# CAN.net
KiCad netlist of a schematic drawn in Altium Designer
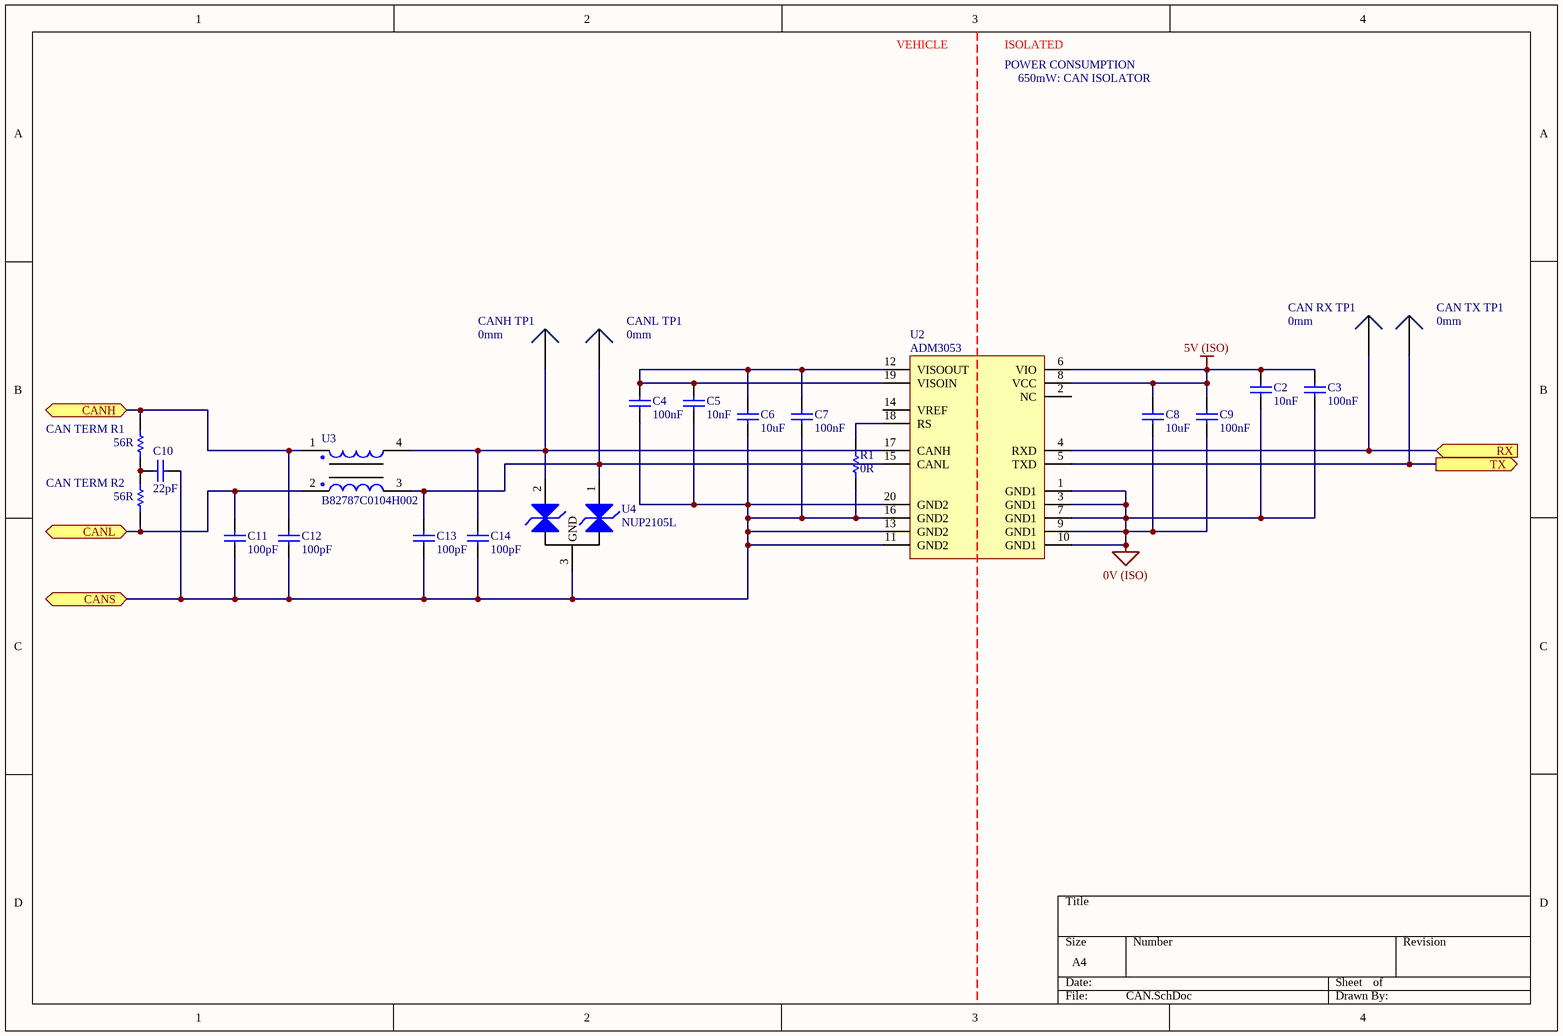
[diagram p0: CAN.SchDoc]

(export (version "E")
  (design (tool "Eeschema 10.0.6"))
  (components
    (comp (ref "C2")
      (value "10nF")
      (footprint "1206")
      (fields
        (field (name "PART NUMBER") "GCM3195C2A103JA16D")
        (field (name "TOLERANCE") "5%")
        (field (name "MANUFACTURER") "muRata")
      )
      (libsource (lib "ts_20-standard-library") (part "Capacitor"))
    )
    (comp (ref "C3")
      (value "100nF")
      (footprint "0805")
      (fields
        (field (name "PART NUMBER") "GCM21BR71E104KA37L")
        (field (name "TOLERANCE") "10%")
        (field (name "MANUFACTURER") "muRata")
      )
      (libsource (lib "ts_20-standard-library") (part "Capacitor"))
    )
    (comp (ref "C4")
      (value "100nF")
      (footprint "0805")
      (fields
        (field (name "PART NUMBER") "GCM21BR71E104KA37L")
        (field (name "TOLERANCE") "10%")
        (field (name "MANUFACTURER") "muRata")
      )
      (libsource (lib "ts_20-standard-library") (part "Capacitor"))
    )
    (comp (ref "C5")
      (value "10nF")
      (footprint "1206")
      (fields
        (field (name "PART NUMBER") "GCM3195C2A103JA16D")
        (field (name "TOLERANCE") "5%")
        (field (name "MANUFACTURER") "muRata")
      )
      (libsource (lib "ts_20-standard-library") (part "Capacitor"))
    )
    (comp (ref "C6")
      (value "10uF")
      (footprint "0805")
      (fields
        (field (name "PART NUMBER") "GRM21BR6YA106KE43L")
        (field (name "TOLERANCE") "10%")
        (field (name "MANUFACTURER") "muRata")
      )
      (libsource (lib "ts_20-standard-library") (part "Capacitor"))
    )
    (comp (ref "C7")
      (value "100nF")
      (footprint "0805")
      (fields
        (field (name "PART NUMBER") "GCM21BR71E104KA37L")
        (field (name "TOLERANCE") "10%")
        (field (name "MANUFACTURER") "muRata")
      )
      (libsource (lib "ts_20-standard-library") (part "Capacitor"))
    )
    (comp (ref "C8")
      (value "10uF")
      (footprint "0805")
      (fields
        (field (name "PART NUMBER") "GRM21BR6YA106KE43L")
        (field (name "TOLERANCE") "10%")
        (field (name "MANUFACTURER") "muRata")
      )
      (libsource (lib "ts_20-standard-library") (part "Capacitor"))
    )
    (comp (ref "C9")
      (value "100nF")
      (footprint "0805")
      (fields
        (field (name "PART NUMBER") "GCM21BR71E104KA37L")
        (field (name "TOLERANCE") "10%")
        (field (name "MANUFACTURER") "muRata")
      )
      (libsource (lib "ts_20-standard-library") (part "Capacitor"))
    )
    (comp (ref "C10")
      (value "22pF")
      (footprint "0805")
      (fields
        (field (name "PART NUMBER") "GCM21B5C1H220JA37L")
        (field (name "TOLERANCE") "5%")
        (field (name "MANUFACTURER") "muRata")
      )
      (libsource (lib "ts_20-standard-library") (part "Capacitor"))
    )
    (comp (ref "C11")
      (value "100pF")
      (footprint "0805")
      (fields
        (field (name "PART NUMBER") "GCM21B5C1H101JA37L")
        (field (name "TOLERANCE") "5%")
        (field (name "MANUFACTURER") "muRata")
      )
      (libsource (lib "ts_20-standard-library") (part "Capacitor"))
    )
    (comp (ref "C12")
      (value "100pF")
      (footprint "0805")
      (fields
        (field (name "PART NUMBER") "GCM21B5C1H101JA37L")
        (field (name "TOLERANCE") "5%")
        (field (name "MANUFACTURER") "muRata")
      )
      (libsource (lib "ts_20-standard-library") (part "Capacitor"))
    )
    (comp (ref "C13")
      (value "100pF")
      (footprint "0805")
      (fields
        (field (name "PART NUMBER") "GCM21B5C1H101JA37L")
        (field (name "TOLERANCE") "5%")
        (field (name "MANUFACTURER") "muRata")
      )
      (libsource (lib "ts_20-standard-library") (part "Capacitor"))
    )
    (comp (ref "C14")
      (value "100pF")
      (footprint "0805")
      (fields
        (field (name "PART NUMBER") "GCM21B5C1H101JA37L")
        (field (name "TOLERANCE") "5%")
        (field (name "MANUFACTURER") "muRata")
      )
      (libsource (lib "ts_20-standard-library") (part "Capacitor"))
    )
    (comp (ref "CAN RX TP1")
      (value "0mm")
      (footprint "SMD Test Point")
      (fields (field (name "PART NUMBER") "SMD Test Point") (field (name "CONTACT") "NA"))
      (libsource (lib "ts_20-standard-connectors") (part "Test Point"))
    )
    (comp (ref "CAN TERM R1")
      (value "56R")
      (footprint "0805")
      (fields
        (field (name "PART NUMBER") "RC0805FR0756RL")
        (field (name "MANUFACTURER") "YAGEO")
        (field (name "TOLERANCE") "0.01")
      )
      (libsource (lib "ts_20-standard-library") (part "Resistor"))
    )
    (comp (ref "CAN TERM R2")
      (value "56R")
      (footprint "0805")
      (fields
        (field (name "PART NUMBER") "RC0805FR0756RL")
        (field (name "MANUFACTURER") "YAGEO")
        (field (name "TOLERANCE") "0.01")
      )
      (libsource (lib "ts_20-standard-library") (part "Resistor"))
    )
    (comp (ref "CAN TX TP1")
      (value "0mm")
      (footprint "SMD Test Point")
      (fields (field (name "PART NUMBER") "SMD Test Point") (field (name "CONTACT") "NA"))
      (libsource (lib "ts_20-standard-connectors") (part "Test Point"))
    )
    (comp (ref "CANH TP1")
      (value "0mm")
      (footprint "SMD Test Point")
      (fields (field (name "PART NUMBER") "SMD Test Point") (field (name "CONTACT") "NA"))
      (libsource (lib "ts_20-standard-connectors") (part "Test Point"))
    )
    (comp (ref "CANL TP1")
      (value "0mm")
      (footprint "SMD Test Point")
      (fields (field (name "PART NUMBER") "SMD Test Point") (field (name "CONTACT") "NA"))
      (libsource (lib "ts_20-standard-connectors") (part "Test Point"))
    )
    (comp (ref "R1")
      (value "0R")
      (footprint "0805")
      (fields
        (field (name "PART NUMBER") "RC0805FR070RL")
        (field (name "MANUFACTURER") "YAGEO")
        (field (name "TOLERANCE") "0.01")
      )
      (libsource (lib "ts_20-standard-library") (part "Resistor"))
    )
    (comp (ref "U2")
      (value "ADM3053")
      (footprint "AD SOIC-W 20")
      (description "Isolated CAN Transceiver")
      (fields
        (field (name "MANUFACTURER") "Analogue Devices")
        (field (name "DIGIKEY PART NUMBER") "ADM3053BRWZ-ND")
      )
      (libsource (lib "ts_20-standard-library") (part "ADM3053"))
    )
    (comp (ref "U3")
      (value "B82787C0104H002")
      (footprint "TDK 4-PC Pad")
      (description "100µH @ 100kHz 2 Line Common Mode Choke Surface Mount 5.8 kOhms @ 10MHz 150mA DCR 2Ohm")
      (fields
        (field (name "MANUFACTURER") "EPCOS (TDK)")
        (field (name "DIGIKEY PART NUMBER") "495-4598-1-ND")
      )
      (libsource (lib "ts_20-standard-library") (part "B82787C0104H002"))
    )
    (comp (ref "U4")
      (value "NUP2105L")
      (footprint "ON SOT-23")
      (description "Dual Line CAN Bus Protector")
      (fields
        (field (name "MANUFACTURER") "ON Semiconductor")
        (field (name "DIGIKEY PART NUMBER") "NUP2105LT1GOSCT-ND")
      )
      (libsource (lib "ts_20-standard-library") (part "NUP2105L"))
    )
  )
  (nets
    (net (code "1") (name "/CANH") (class "Default")
      (node (ref "C12") (pin "2") (pinfunction "2_2") (pintype "passive"))
      (node (ref "CAN TERM R1") (pin "2") (pinfunction "2_2") (pintype "passive"))
      (node (ref "U3") (pin "1") (pinfunction "1_1") (pintype "passive"))
    )
    (net (code "2") (name "/CANL") (class "Default")
      (node (ref "C11") (pin "2") (pinfunction "2_2") (pintype "passive"))
      (node (ref "CAN TERM R2") (pin "1") (pinfunction "1_1") (pintype "passive"))
      (node (ref "U3") (pin "2") (pinfunction "2_2") (pintype "passive"))
    )
    (net (code "3") (name "/CANS") (class "Default")
      (node (ref "C10") (pin "1") (pinfunction "1_1") (pintype "passive"))
      (node (ref "C11") (pin "1") (pinfunction "1_1") (pintype "passive"))
      (node (ref "C12") (pin "1") (pinfunction "1_1") (pintype "passive"))
      (node (ref "C13") (pin "1") (pinfunction "1_1") (pintype "passive"))
      (node (ref "C14") (pin "1") (pinfunction "1_1") (pintype "passive"))
      (node (ref "C4") (pin "1") (pinfunction "1_1") (pintype "passive"))
      (node (ref "C5") (pin "1") (pinfunction "1_1") (pintype "passive"))
      (node (ref "C6") (pin "1") (pinfunction "1_1") (pintype "passive"))
      (node (ref "C7") (pin "1") (pinfunction "1_1") (pintype "passive"))
      (node (ref "R1") (pin "1") (pinfunction "1_1") (pintype "passive"))
      (node (ref "U2") (pin "11") (pinfunction "GND2_11") (pintype "passive"))
      (node (ref "U2") (pin "13") (pinfunction "GND2_13") (pintype "passive"))
      (node (ref "U2") (pin "16") (pinfunction "GND2_16") (pintype "passive"))
      (node (ref "U2") (pin "20") (pinfunction "GND2_20") (pintype "passive"))
      (node (ref "U4") (pin "3") (pinfunction "GND_3") (pintype "power_in"))
    )
    (net (code "4") (name "/RX") (class "Default")
      (node (ref "CAN RX TP1") (pin "1") (pinfunction "1_1") (pintype "passive"))
      (node (ref "U2") (pin "4") (pinfunction "RXD_4") (pintype "passive"))
    )
    (net (code "5") (name "/TX") (class "Default")
      (node (ref "CAN TX TP1") (pin "1") (pinfunction "1_1") (pintype "passive"))
      (node (ref "U2") (pin "5") (pinfunction "TXD_5") (pintype "passive"))
    )
    (net (code "6") (name "0V (ISO)") (class "Default")
      (node (ref "C2") (pin "1") (pinfunction "1_1") (pintype "passive"))
      (node (ref "C3") (pin "1") (pinfunction "1_1") (pintype "passive"))
      (node (ref "C8") (pin "1") (pinfunction "1_1") (pintype "passive"))
      (node (ref "C9") (pin "1") (pinfunction "1_1") (pintype "passive"))
      (node (ref "U2") (pin "1") (pinfunction "GND1_1") (pintype "passive"))
      (node (ref "U2") (pin "10") (pinfunction "GND1_10") (pintype "passive"))
      (node (ref "U2") (pin "3") (pinfunction "GND1_3") (pintype "passive"))
      (node (ref "U2") (pin "7") (pinfunction "GND1_7") (pintype "passive"))
      (node (ref "U2") (pin "9") (pinfunction "GND1_9") (pintype "passive"))
    )
    (net (code "7") (name "5V (ISO)") (class "Default")
      (node (ref "C2") (pin "2") (pinfunction "2_2") (pintype "passive"))
      (node (ref "C3") (pin "2") (pinfunction "2_2") (pintype "passive"))
      (node (ref "C8") (pin "2") (pinfunction "2_2") (pintype "passive"))
      (node (ref "C9") (pin "2") (pinfunction "2_2") (pintype "passive"))
      (node (ref "U2") (pin "6") (pinfunction "VIO_6") (pintype "passive"))
      (node (ref "U2") (pin "8") (pinfunction "VCC_8") (pintype "passive"))
    )
    (net (code "8") (name "Net-(C10-Pad2)") (class "Default")
      (node (ref "C10") (pin "2") (pinfunction "2_2") (pintype "passive"))
      (node (ref "CAN TERM R1") (pin "1") (pinfunction "1_1") (pintype "passive"))
      (node (ref "CAN TERM R2") (pin "2") (pinfunction "2_2") (pintype "passive"))
    )
    (net (code "9") (name "Net-(U2-CANH)") (class "Default")
      (node (ref "C14") (pin "2") (pinfunction "2_2") (pintype "passive"))
      (node (ref "CANH TP1") (pin "1") (pinfunction "1_1") (pintype "passive"))
      (node (ref "U2") (pin "17") (pinfunction "CANH_17") (pintype "passive"))
      (node (ref "U3") (pin "4") (pinfunction "4_4") (pintype "passive"))
      (node (ref "U4") (pin "2") (pinfunction "CAN_L_2") (pintype "passive"))
    )
    (net (code "10") (name "Net-(U2-CANL)") (class "Default")
      (node (ref "C13") (pin "2") (pinfunction "2_2") (pintype "passive"))
      (node (ref "CANL TP1") (pin "1") (pinfunction "1_1") (pintype "passive"))
      (node (ref "U2") (pin "15") (pinfunction "CANL_15") (pintype "passive"))
      (node (ref "U3") (pin "3") (pinfunction "3_3") (pintype "power_in"))
      (node (ref "U4") (pin "1") (pinfunction "CAN_H_1") (pintype "passive"))
    )
    (net (code "11") (name "Net-(U2-RS)") (class "Default")
      (node (ref "R1") (pin "2") (pinfunction "2_2") (pintype "passive"))
      (node (ref "U2") (pin "18") (pinfunction "RS_18") (pintype "passive"))
    )
    (net (code "12") (name "Net-(U2-VISOIN)") (class "Default")
      (node (ref "C4") (pin "2") (pinfunction "2_2") (pintype "passive"))
      (node (ref "C5") (pin "2") (pinfunction "2_2") (pintype "passive"))
      (node (ref "C6") (pin "2") (pinfunction "2_2") (pintype "passive"))
      (node (ref "C7") (pin "2") (pinfunction "2_2") (pintype "passive"))
      (node (ref "U2") (pin "12") (pinfunction "VISOOUT_12") (pintype "passive"))
      (node (ref "U2") (pin "19") (pinfunction "VISOIN_19") (pintype "passive"))
    )
    (net (code "13") (name "unconnected-(U2-NC-Pad2)") (class "Default")
      (node (ref "U2") (pin "2") (pinfunction "NC_2") (pintype "passive"))
    )
    (net (code "14") (name "unconnected-(U2-VREF-Pad14)") (class "Default")
      (node (ref "U2") (pin "14") (pinfunction "VREF_14") (pintype "passive"))
    )
  )
)
